# LiPo_Charger.net
KiCad netlist of a schematic drawn in Altium Designer
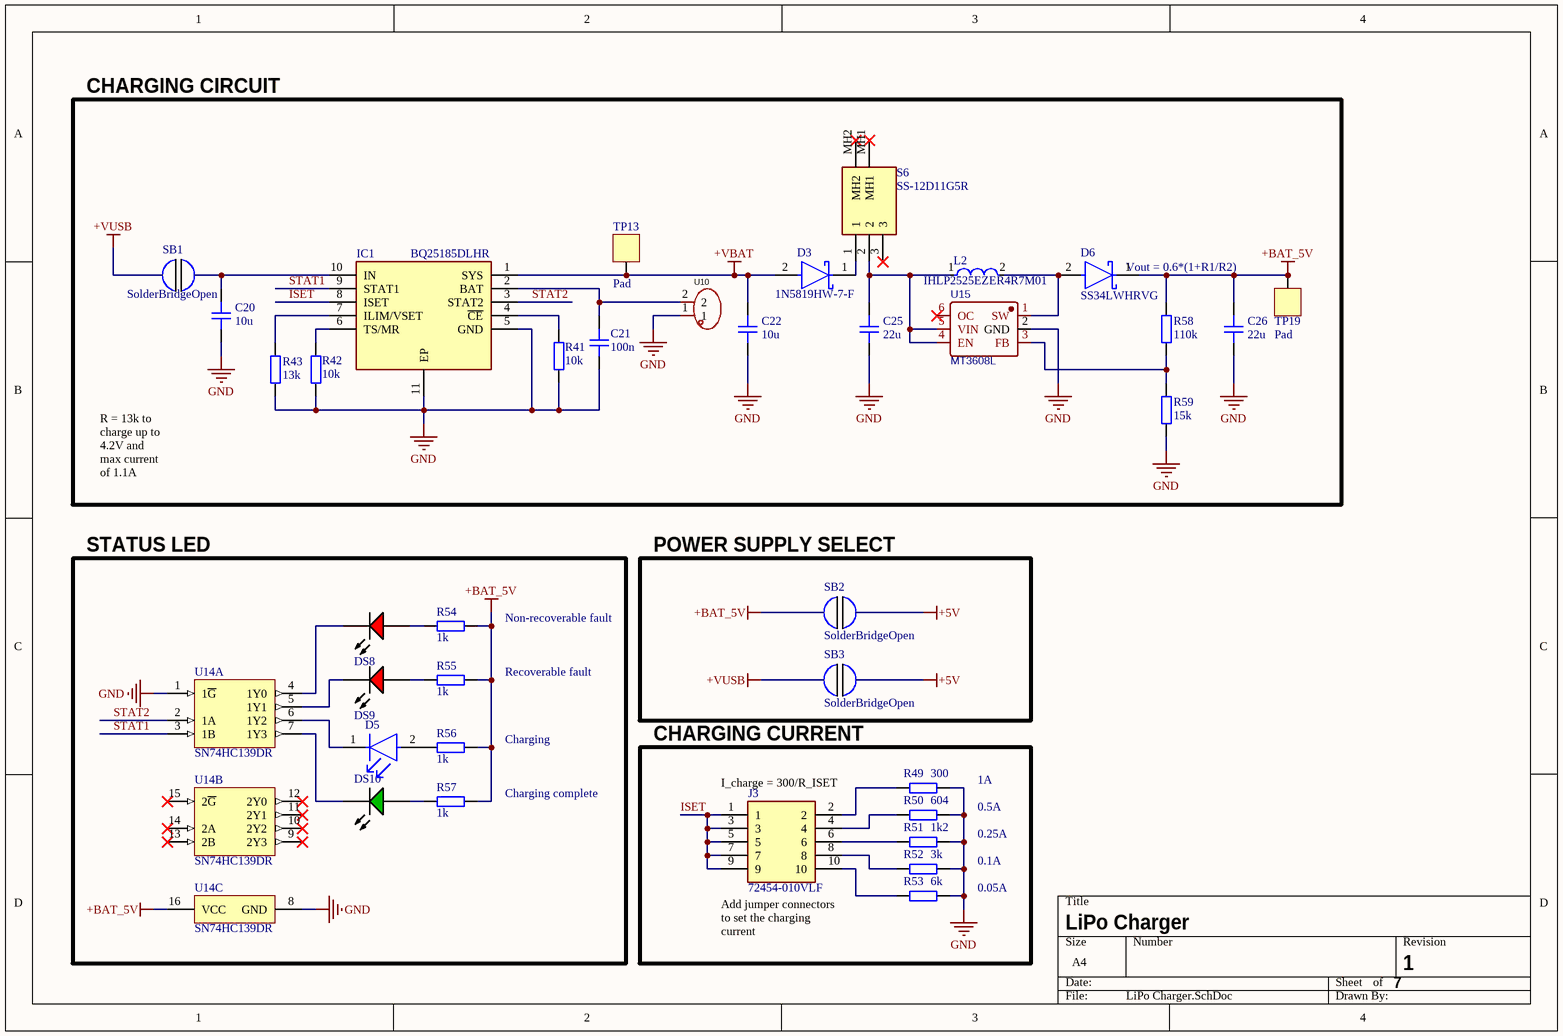
[diagram p0: LiPo Charger.SchDoc]

(export (version "E")
  (design (tool "Eeschema 10.0.6"))
  (components
    (comp (ref "C20")
      (value "10u")
      (footprint "CAP_0402")
      (description "Capacitor SMD 0402")
      (fields (field (name "Comment") "CL05A106MQ5NUNC"))
      (libsource (lib "Schematic-Lib-PhilsLab") (part "CAP_0402"))
    )
    (comp (ref "C21")
      (value "CL05B104KB54PNC")
      (footprint "CAP_0402")
      (description "Capacitor SMD 0402")
      (fields (field (name "RATING") "100n"))
      (libsource (lib "Schematic-Lib-PhilsLab") (part "CAP_0402"))
    )
    (comp (ref "C22")
      (value "10u")
      (footprint "CAP_0402")
      (description "Capacitor SMD 0402")
      (fields (field (name "Comment") "CL05A106MQ5NUNC"))
      (libsource (lib "Schematic-Lib-PhilsLab") (part "CAP_0402"))
    )
    (comp (ref "C25")
      (value "GRM158R61A226ME15D")
      (footprint "CAP_0402")
      (description "Capacitor SMD 0402")
      (fields (field (name "RATING") "22u"))
      (libsource (lib "Schematic-Lib-PhilsLab") (part "CAP_0402"))
    )
    (comp (ref "C26")
      (value "GRM158R61A226ME15D")
      (footprint "CAP_0402")
      (description "Capacitor SMD 0402")
      (fields (field (name "RATING") "22u"))
      (libsource (lib "Schematic-Lib-PhilsLab") (part "CAP_0402"))
    )
    (comp (ref "D3")
      (value "1N5819HW-7-F")
      (footprint "FP-SOD123-IPC_A")
      (description "DIODE SCHOTTKY 40V 1A SOD123")
      (libsource (lib "Altium Content Vault") (part "1d6ec82d83fb6aee721767c19dac4b9"))
    )
    (comp (ref "D5")
      (value "LTST-C170KFKT")
      (footprint "FP-LTST-C170KFKT-MFG")
      (description "LED ORANGE CLEAR SMD")
      (libsource (lib "Altium Content Vault") (part "8706943c75ba83719d021d2fdc84c58"))
    )
    (comp (ref "D6")
      (value "SS34LWHRVG")
      (footprint "FP-SS34LWH-MFG")
      (description "DIODE SCHOTTKY 40V 3A SOD123W")
      (libsource (lib "Altium Content Vault") (part "1d6ec82d83fb6aee721767c19dac4b9"))
    )
    (comp (ref "DS8")
      (value "LTST-C170KRKT")
      (footprint "LTST-C170KRKT_V")
      (description "LED Red, 75 mW, 54 mcd, -55 to 85 degC, 2-Pin SMD, RoHS, Tape and Reel")
      (fields (field (name "MANUFACTURER") "Lite-On"))
      (libsource (lib "Altium Content Vault") (part "LED-RED-AK-2"))
    )
    (comp (ref "DS9")
      (value "LTST-C170KRKT")
      (footprint "LTST-C170KRKT_V")
      (description "LED Red, 75 mW, 54 mcd, -55 to 85 degC, 2-Pin SMD, RoHS, Tape and Reel")
      (fields (field (name "MANUFACTURER") "Lite-On"))
      (libsource (lib "Altium Content Vault") (part "LED-RED-AK-2"))
    )
    (comp (ref "DS10")
      (value "LTST-C170KGKT")
      (footprint "LTST-LTST-C170KGKT-2_V")
      (description "Ultra Bright AlInGaP Chip LED, 75 mW, -55 to 85 degC, 2-Pin SMD (0805), RoHS, Tape and Reel")
      (fields (field (name "MANUFACTURER") "Lite-On"))
      (libsource (lib "Altium Content Vault") (part "LED-GREEN-KA-2"))
    )
    (comp (ref "IC1")
      (value "BQ25185DLHR")
      (footprint "JLCPCB_parts_library:SON40P220X200X80-11N")
      (description "Integrated Circuit")
      (fields (field (name "MOUSER PART NUMBER") "595-BQ25185DLHR"))
      (libsource (lib "JLCPCB_parts_library") (part "BQ25185DLHR"))
    )
    (comp (ref "J3")
      (value "72454-010VLF")
      (footprint "JLCPCB_parts_library:72454010VLF")
      (description "Connector")
      (fields (field (name "MOUSER PART NUMBER") "649-72454-010VLF"))
      (libsource (lib "JLCPCB_parts_library") (part "72454-010VLF"))
    )
    (comp (ref "L2")
      (value "IHLP2525EZER4R7M01")
      (footprint "FP-IHLP-2525EZ-FP_2_413x3-MFG")
      (description "Commercial Inductors, High Saturation Series 4.7uH 6.5A 30.3mΩ 20%")
      (fields (field (name "TOLERANCE") "20%"))
      (libsource (lib "Altium Content Vault") (part "725321dda6339637d4d059423bc1c3c"))
    )
    (comp (ref "R41")
      (value "10k")
      (footprint "RES_0402")
      (description "Resistor SMD 0402")
      (fields (field (name "Comment") "0402WGF1002TCE"))
      (libsource (lib "Schematic-Lib-PhilsLab") (part "RES_0402"))
    )
    (comp (ref "R42")
      (value "10k")
      (footprint "RES_0402")
      (description "Resistor SMD 0402")
      (fields (field (name "Comment") "0402WGF1002TCE"))
      (libsource (lib "Schematic-Lib-PhilsLab") (part "RES_0402"))
    )
    (comp (ref "R43")
      (value "0603WAF1302T5E")
      (footprint "RES_0603")
      (description "Resistor SMD 0603")
      (fields (field (name "RESISTANCE") "13k"))
      (libsource (lib "Schematic-Lib-PhilsLab") (part "RES_0603"))
    )
    (comp (ref "R49")
      (value "0402WGF3000TCE")
      (footprint "RES_0402")
      (description "Resistor SMD 0402")
      (fields (field (name "RESISTANCE") "300"))
      (libsource (lib "Schematic-Lib-PhilsLab") (part "RES_0402"))
    )
    (comp (ref "R50")
      (value "CL0402FN604RP")
      (footprint "RES_0402")
      (description "Resistor SMD 0402")
      (fields (field (name "RESISTANCE") "604"))
      (libsource (lib "Schematic-Lib-PhilsLab") (part "RES_0402"))
    )
    (comp (ref "R51")
      (value "0402WGF1201TCE")
      (footprint "RES_0402")
      (description "Resistor SMD 0402")
      (fields (field (name "RESISTANCE") "1k2"))
      (libsource (lib "Schematic-Lib-PhilsLab") (part "RES_0402"))
    )
    (comp (ref "R52")
      (value "FRC0402F3001TS")
      (footprint "RES_0402")
      (description "Resistor SMD 0402")
      (fields (field (name "RESISTANCE") "3k"))
      (libsource (lib "Schematic-Lib-PhilsLab") (part "RES_0402"))
    )
    (comp (ref "R53")
      (value "RC0402FR-076K04L")
      (footprint "RES_0402")
      (description "Resistor SMD 0402")
      (fields (field (name "RESISTANCE") "6k"))
      (libsource (lib "Schematic-Lib-PhilsLab") (part "RES_0402"))
    )
    (comp (ref "R54")
      (value "1k")
      (footprint "RES_0402")
      (description "Resistor SMD 0402")
      (fields (field (name "Comment") "0402WGF1001TCE"))
      (libsource (lib "Schematic-Lib-PhilsLab") (part "RES_0402"))
    )
    (comp (ref "R55")
      (value "1k")
      (footprint "RES_0402")
      (description "Resistor SMD 0402")
      (fields (field (name "Comment") "0402WGF1001TCE"))
      (libsource (lib "Schematic-Lib-PhilsLab") (part "RES_0402"))
    )
    (comp (ref "R56")
      (value "1k")
      (footprint "RES_0402")
      (description "Resistor SMD 0402")
      (fields (field (name "Comment") "0402WGF1001TCE"))
      (libsource (lib "Schematic-Lib-PhilsLab") (part "RES_0402"))
    )
    (comp (ref "R57")
      (value "1k")
      (footprint "RES_0402")
      (description "Resistor SMD 0402")
      (fields (field (name "Comment") "0402WGF1001TCE"))
      (libsource (lib "Schematic-Lib-PhilsLab") (part "RES_0402"))
    )
    (comp (ref "R58")
      (value "110k")
      (footprint "RES_0402")
      (description "Resistor SMD 0402")
      (fields (field (name "Comment") "RC0402FR-07110KL"))
      (libsource (lib "Schematic-Lib-PhilsLab") (part "RES_0402"))
    )
    (comp (ref "R59")
      (value "15k")
      (footprint "RES_0402")
      (description "Resistor SMD 0402")
      (fields (field (name "Comment") "0402WGF1502TCE"))
      (libsource (lib "Schematic-Lib-PhilsLab") (part "RES_0402"))
    )
    (comp (ref "S6")
      (value "SS-12D11G5R")
      (footprint "JLCPCB_parts_library:SS12D11G5R")
      (description "Switch")
      (libsource (lib "JLCPCB_parts_library") (part "SS-12D11G5R"))
    )
    (comp (ref "SB1")
      (value "SolderBridgeOpen")
      (footprint "PCBComponent_1")
      (description "Close the brige with solder")
      (libsource (lib "SolderJumper") (part "SolderBridgeOpen"))
    )
    (comp (ref "SB2")
      (value "SolderBridgeOpen")
      (footprint "PCBComponent_1")
      (description "Close the brige with solder")
      (libsource (lib "SolderJumper") (part "SolderBridgeOpen"))
    )
    (comp (ref "SB3")
      (value "SolderBridgeOpen")
      (footprint "PCBComponent_1")
      (description "Close the brige with solder")
      (libsource (lib "SolderJumper") (part "SolderBridgeOpen"))
    )
    (comp (ref "TP13")
      (value "Pad")
      (footprint "PAD_SQ_2MM")
      (description "Test Point Square 2mm")
      (libsource (lib "") (part "PAD_SQ_2MM_1"))
    )
    (comp (ref "TP19")
      (value "Pad")
      (footprint "PAD_SQ_2MM")
      (description "Test Point Square 2mm")
      (libsource (lib "Schematic-Lib-PhilsLab") (part "PAD_SQ_2MM"))
    )
    (comp (ref "U10")
      (value "DB125-3.81-2P-RD-S")
      (footprint "CONN-TH_DB125-3.81-2P-RD")
      (fields (field (name "MANUFACTURER") "DORABO(地博电气)"))
      (libsource (lib "JLCPCB_parts_library") (part "DB125-3.81-2P-RD-S"))
    )
    (comp (ref "U14")
      (value "SN74HC139DR")
      (footprint "D0016A_L")
      (description "Dual 2-Line To 4-Line Decoders/Demultiplexers, D0016A, LARGE T&R")
      (fields
        (field (name "MANUFACTURER") "Texas Instruments")
        (field (name "GENERIC PART NUMBER") "SN74HC139")
      )
      (libsource (lib "Altium Content Vault") (part "TI-CD_SNX4XXX139-16"))
    )
    (comp (ref "U15")
      (value "MT3608L")
      (footprint "SOT-23-6_L2.9-W1.6-P0.95-LS2.8-BL_3")
      (fields (field (name "MANUFACTURER") "西安航天民芯") (field (name "CONTRIBUTOR") "LCSC"))
      (libsource (lib "JLCPCB_parts_library") (part "MT3608L"))
    )
  )
  (nets
    (net (code "1") (name "+5V") (class "Default")
      (node (ref "SB2") (pin "2") (pinfunction "2_2") (pintype "passive"))
      (node (ref "SB3") (pin "2") (pinfunction "2_2") (pintype "passive"))
    )
    (net (code "2") (name "+BAT_5V") (class "Default")
      (node (ref "C26") (pin "2") (pinfunction "2_2") (pintype "passive"))
      (node (ref "D6") (pin "1") (pinfunction "C_1") (pintype "passive"))
      (node (ref "R54") (pin "1") (pinfunction "1_1") (pintype "passive"))
      (node (ref "R55") (pin "1") (pinfunction "1_1") (pintype "passive"))
      (node (ref "R56") (pin "1") (pinfunction "1_1") (pintype "passive"))
      (node (ref "R57") (pin "1") (pinfunction "1_1") (pintype "passive"))
      (node (ref "R58") (pin "2") (pinfunction "2_2") (pintype "passive"))
      (node (ref "SB2") (pin "1") (pinfunction "1_1") (pintype "passive"))
      (node (ref "TP19") (pin "1") (pinfunction "1_1") (pintype "passive"))
      (node (ref "U14") (pin "16") (pinfunction "VCC_16") (pintype "power_in"))
    )
    (net (code "3") (name "+VBAT") (class "Default")
      (node (ref "C22") (pin "2") (pinfunction "2_2") (pintype "passive"))
      (node (ref "D3") (pin "2") (pinfunction "A_2") (pintype "passive"))
      (node (ref "IC1") (pin "1") (pinfunction "SYS_1") (pintype "passive"))
      (node (ref "TP13") (pin "1") (pinfunction "1_1") (pintype "passive"))
    )
    (net (code "4") (name "+VUSB") (class "Default")
      (node (ref "SB1") (pin "1") (pinfunction "1_1") (pintype "passive"))
      (node (ref "SB3") (pin "1") (pinfunction "1_1") (pintype "passive"))
    )
    (net (code "5") (name "/ISET") (class "Default")
      (node (ref "IC1") (pin "8") (pinfunction "ISET_8") (pintype "passive"))
      (node (ref "J3") (pin "1") (pinfunction "1_1") (pintype "passive"))
      (node (ref "J3") (pin "3") (pinfunction "3_3") (pintype "passive"))
      (node (ref "J3") (pin "5") (pinfunction "5_5") (pintype "passive"))
      (node (ref "J3") (pin "7") (pinfunction "7_7") (pintype "passive"))
      (node (ref "J3") (pin "9") (pinfunction "9_9") (pintype "passive"))
    )
    (net (code "6") (name "/STAT1") (class "Default")
      (node (ref "IC1") (pin "9") (pinfunction "STAT1_9") (pintype "passive"))
      (node (ref "U14") (pin "3") (pinfunction "1B_3") (pintype "input"))
    )
    (net (code "7") (name "/STAT2") (class "Default")
      (node (ref "IC1") (pin "3") (pinfunction "STAT2_3") (pintype "passive"))
      (node (ref "U14") (pin "2") (pinfunction "1A_2") (pintype "input"))
    )
    (net (code "8") (name "GND") (class "Default")
      (node (ref "C20") (pin "1") (pinfunction "1_1") (pintype "passive"))
      (node (ref "C21") (pin "2") (pinfunction "2_2") (pintype "passive"))
      (node (ref "C22") (pin "1") (pinfunction "1_1") (pintype "passive"))
      (node (ref "C25") (pin "1") (pinfunction "1_1") (pintype "passive"))
      (node (ref "C26") (pin "1") (pinfunction "1_1") (pintype "passive"))
      (node (ref "IC1") (pin "11") (pinfunction "EP_11") (pintype "passive"))
      (node (ref "IC1") (pin "5") (pinfunction "GND_5") (pintype "passive"))
      (node (ref "R41") (pin "1") (pinfunction "1_1") (pintype "passive"))
      (node (ref "R42") (pin "1") (pinfunction "1_1") (pintype "passive"))
      (node (ref "R43") (pin "1") (pinfunction "1_1") (pintype "passive"))
      (node (ref "R49") (pin "2") (pinfunction "2_2") (pintype "passive"))
      (node (ref "R50") (pin "2") (pinfunction "2_2") (pintype "passive"))
      (node (ref "R51") (pin "2") (pinfunction "2_2") (pintype "passive"))
      (node (ref "R52") (pin "2") (pinfunction "2_2") (pintype "passive"))
      (node (ref "R53") (pin "2") (pinfunction "2_2") (pintype "passive"))
      (node (ref "R59") (pin "1") (pinfunction "1_1") (pintype "passive"))
      (node (ref "U10") (pin "1") (pinfunction "1_1") (pintype "passive"))
      (node (ref "U14") (pin "1") (pinfunction "1~{G}_1") (pintype "input"))
      (node (ref "U14") (pin "8") (pinfunction "GND_8") (pintype "power_in"))
      (node (ref "U15") (pin "2") (pinfunction "GND_2") (pintype "passive"))
    )
    (net (code "9") (name "Net-(D3-C)") (class "Default")
      (node (ref "D3") (pin "1") (pinfunction "C_1") (pintype "passive"))
      (node (ref "S6") (pin "1") (pinfunction "1_1") (pintype "passive"))
    )
    (net (code "10") (name "Net-(D5-A)") (class "Default")
      (node (ref "D5") (pin "2") (pinfunction "A_2") (pintype "passive"))
      (node (ref "R56") (pin "2") (pinfunction "2_2") (pintype "passive"))
    )
    (net (code "11") (name "Net-(D5-C)") (class "Default")
      (node (ref "D5") (pin "1") (pinfunction "C_1") (pintype "passive"))
      (node (ref "U14") (pin "6") (pinfunction "1Y2_6") (pintype "output"))
    )
    (net (code "12") (name "Net-(D6-A)") (class "Default")
      (node (ref "D6") (pin "2") (pinfunction "A_2") (pintype "passive"))
      (node (ref "L2") (pin "2") (pinfunction "2_2") (pintype "passive"))
      (node (ref "U15") (pin "1") (pinfunction "SW_1") (pintype "passive"))
    )
    (net (code "13") (name "Net-(DS8-A)") (class "Default")
      (node (ref "DS8") (pin "1") (pinfunction "A_1") (pintype "passive"))
      (node (ref "R54") (pin "2") (pinfunction "2_2") (pintype "passive"))
    )
    (net (code "14") (name "Net-(DS8-K)") (class "Default")
      (node (ref "DS8") (pin "2") (pinfunction "K_2") (pintype "passive"))
      (node (ref "U14") (pin "4") (pinfunction "1Y0_4") (pintype "output"))
    )
    (net (code "15") (name "Net-(DS9-A)") (class "Default")
      (node (ref "DS9") (pin "1") (pinfunction "A_1") (pintype "passive"))
      (node (ref "R55") (pin "2") (pinfunction "2_2") (pintype "passive"))
    )
    (net (code "16") (name "Net-(DS9-K)") (class "Default")
      (node (ref "DS9") (pin "2") (pinfunction "K_2") (pintype "passive"))
      (node (ref "U14") (pin "5") (pinfunction "1Y1_5") (pintype "output"))
    )
    (net (code "17") (name "Net-(DS10-A)") (class "Default")
      (node (ref "DS10") (pin "2") (pinfunction "A_2") (pintype "passive"))
      (node (ref "R57") (pin "2") (pinfunction "2_2") (pintype "passive"))
    )
    (net (code "18") (name "Net-(DS10-K)") (class "Default")
      (node (ref "DS10") (pin "1") (pinfunction "K_1") (pintype "passive"))
      (node (ref "U14") (pin "7") (pinfunction "1Y3_7") (pintype "output"))
    )
    (net (code "19") (name "Net-(IC1-BAT)") (class "Default")
      (node (ref "C21") (pin "1") (pinfunction "1_1") (pintype "passive"))
      (node (ref "IC1") (pin "2") (pinfunction "BAT_2") (pintype "passive"))
      (node (ref "U10") (pin "2") (pinfunction "2_2") (pintype "passive"))
    )
    (net (code "20") (name "Net-(IC1-ILIM{slash}VSET)") (class "Default")
      (node (ref "IC1") (pin "7") (pinfunction "ILIM/VSET_7") (pintype "passive"))
      (node (ref "R43") (pin "2") (pinfunction "2_2") (pintype "passive"))
    )
    (net (code "21") (name "Net-(IC1-IN)") (class "Default")
      (node (ref "C20") (pin "2") (pinfunction "2_2") (pintype "passive"))
      (node (ref "IC1") (pin "10") (pinfunction "IN_10") (pintype "passive"))
      (node (ref "SB1") (pin "2") (pinfunction "2_2") (pintype "passive"))
    )
    (net (code "22") (name "Net-(IC1-TS{slash}MR)") (class "Default")
      (node (ref "IC1") (pin "6") (pinfunction "TS/MR_6") (pintype "passive"))
      (node (ref "R42") (pin "2") (pinfunction "2_2") (pintype "passive"))
    )
    (net (code "23") (name "Net-(IC1-~{CE})") (class "Default")
      (node (ref "IC1") (pin "4") (pinfunction "~{CE}_4") (pintype "passive"))
      (node (ref "R41") (pin "2") (pinfunction "2_2") (pintype "passive"))
    )
    (net (code "24") (name "Net-(J3-Pad2)") (class "Default")
      (node (ref "J3") (pin "2") (pinfunction "2_2") (pintype "passive"))
      (node (ref "R49") (pin "1") (pinfunction "1_1") (pintype "passive"))
    )
    (net (code "25") (name "Net-(J3-Pad4)") (class "Default")
      (node (ref "J3") (pin "4") (pinfunction "4_4") (pintype "passive"))
      (node (ref "R50") (pin "1") (pinfunction "1_1") (pintype "passive"))
    )
    (net (code "26") (name "Net-(J3-Pad6)") (class "Default")
      (node (ref "J3") (pin "6") (pinfunction "6_6") (pintype "passive"))
      (node (ref "R51") (pin "1") (pinfunction "1_1") (pintype "passive"))
    )
    (net (code "27") (name "Net-(J3-Pad8)") (class "Default")
      (node (ref "J3") (pin "8") (pinfunction "8_8") (pintype "passive"))
      (node (ref "R52") (pin "1") (pinfunction "1_1") (pintype "passive"))
    )
    (net (code "28") (name "Net-(J3-Pad10)") (class "Default")
      (node (ref "J3") (pin "10") (pinfunction "10_10") (pintype "passive"))
      (node (ref "R53") (pin "1") (pinfunction "1_1") (pintype "passive"))
    )
    (net (code "29") (name "Net-(U15-EN)") (class "Default")
      (node (ref "C25") (pin "2") (pinfunction "2_2") (pintype "passive"))
      (node (ref "L2") (pin "1") (pinfunction "1_1") (pintype "passive"))
      (node (ref "S6") (pin "2") (pinfunction "2_2") (pintype "passive"))
      (node (ref "U15") (pin "4") (pinfunction "EN_4") (pintype "passive"))
      (node (ref "U15") (pin "5") (pinfunction "VIN_5") (pintype "passive"))
    )
    (net (code "30") (name "Net-(U15-FB)") (class "Default")
      (node (ref "R58") (pin "1") (pinfunction "1_1") (pintype "passive"))
      (node (ref "R59") (pin "2") (pinfunction "2_2") (pintype "passive"))
      (node (ref "U15") (pin "3") (pinfunction "FB_3") (pintype "passive"))
    )
    (net (code "31") (name "unconnected-(S6-Pad3)") (class "Default")
      (node (ref "S6") (pin "3") (pinfunction "3_3") (pintype "passive+no_connect"))
    )
    (net (code "32") (name "unconnected-(S6-PadMH1)") (class "Default")
      (node (ref "S6") (pin "MH1") (pinfunction "MH1_MH1") (pintype "passive+no_connect"))
    )
    (net (code "33") (name "unconnected-(S6-PadMH2)") (class "Default")
      (node (ref "S6") (pin "MH2") (pinfunction "MH2_MH2") (pintype "passive+no_connect"))
    )
    (net (code "34") (name "unconnected-(U14B-2A-Pad14)") (class "Default")
      (node (ref "U14") (pin "14") (pinfunction "2A_14") (pintype "input+no_connect"))
    )
    (net (code "35") (name "unconnected-(U14B-2B-Pad13)") (class "Default")
      (node (ref "U14") (pin "13") (pinfunction "2B_13") (pintype "input+no_connect"))
    )
    (net (code "36") (name "unconnected-(U14B-2Y0-Pad12)") (class "Default")
      (node (ref "U14") (pin "12") (pinfunction "2Y0_12") (pintype "output+no_connect"))
    )
    (net (code "37") (name "unconnected-(U14B-2Y1-Pad11)") (class "Default")
      (node (ref "U14") (pin "11") (pinfunction "2Y1_11") (pintype "output+no_connect"))
    )
    (net (code "38") (name "unconnected-(U14B-2Y2-Pad10)") (class "Default")
      (node (ref "U14") (pin "10") (pinfunction "2Y2_10") (pintype "output+no_connect"))
    )
    (net (code "39") (name "unconnected-(U14B-2Y3-Pad9)") (class "Default")
      (node (ref "U14") (pin "9") (pinfunction "2Y3_9") (pintype "output+no_connect"))
    )
    (net (code "40") (name "unconnected-(U14B-2~{G}-Pad15)") (class "Default")
      (node (ref "U14") (pin "15") (pinfunction "2~{G}_15") (pintype "input+no_connect"))
    )
    (net (code "41") (name "unconnected-(U15-OC-Pad6)") (class "Default")
      (node (ref "U15") (pin "6") (pinfunction "OC_6") (pintype "passive+no_connect"))
    )
  )
)
